# Thesis_HarvestEvaluator.net
KiCad netlist of a schematic drawn in Altium Designer
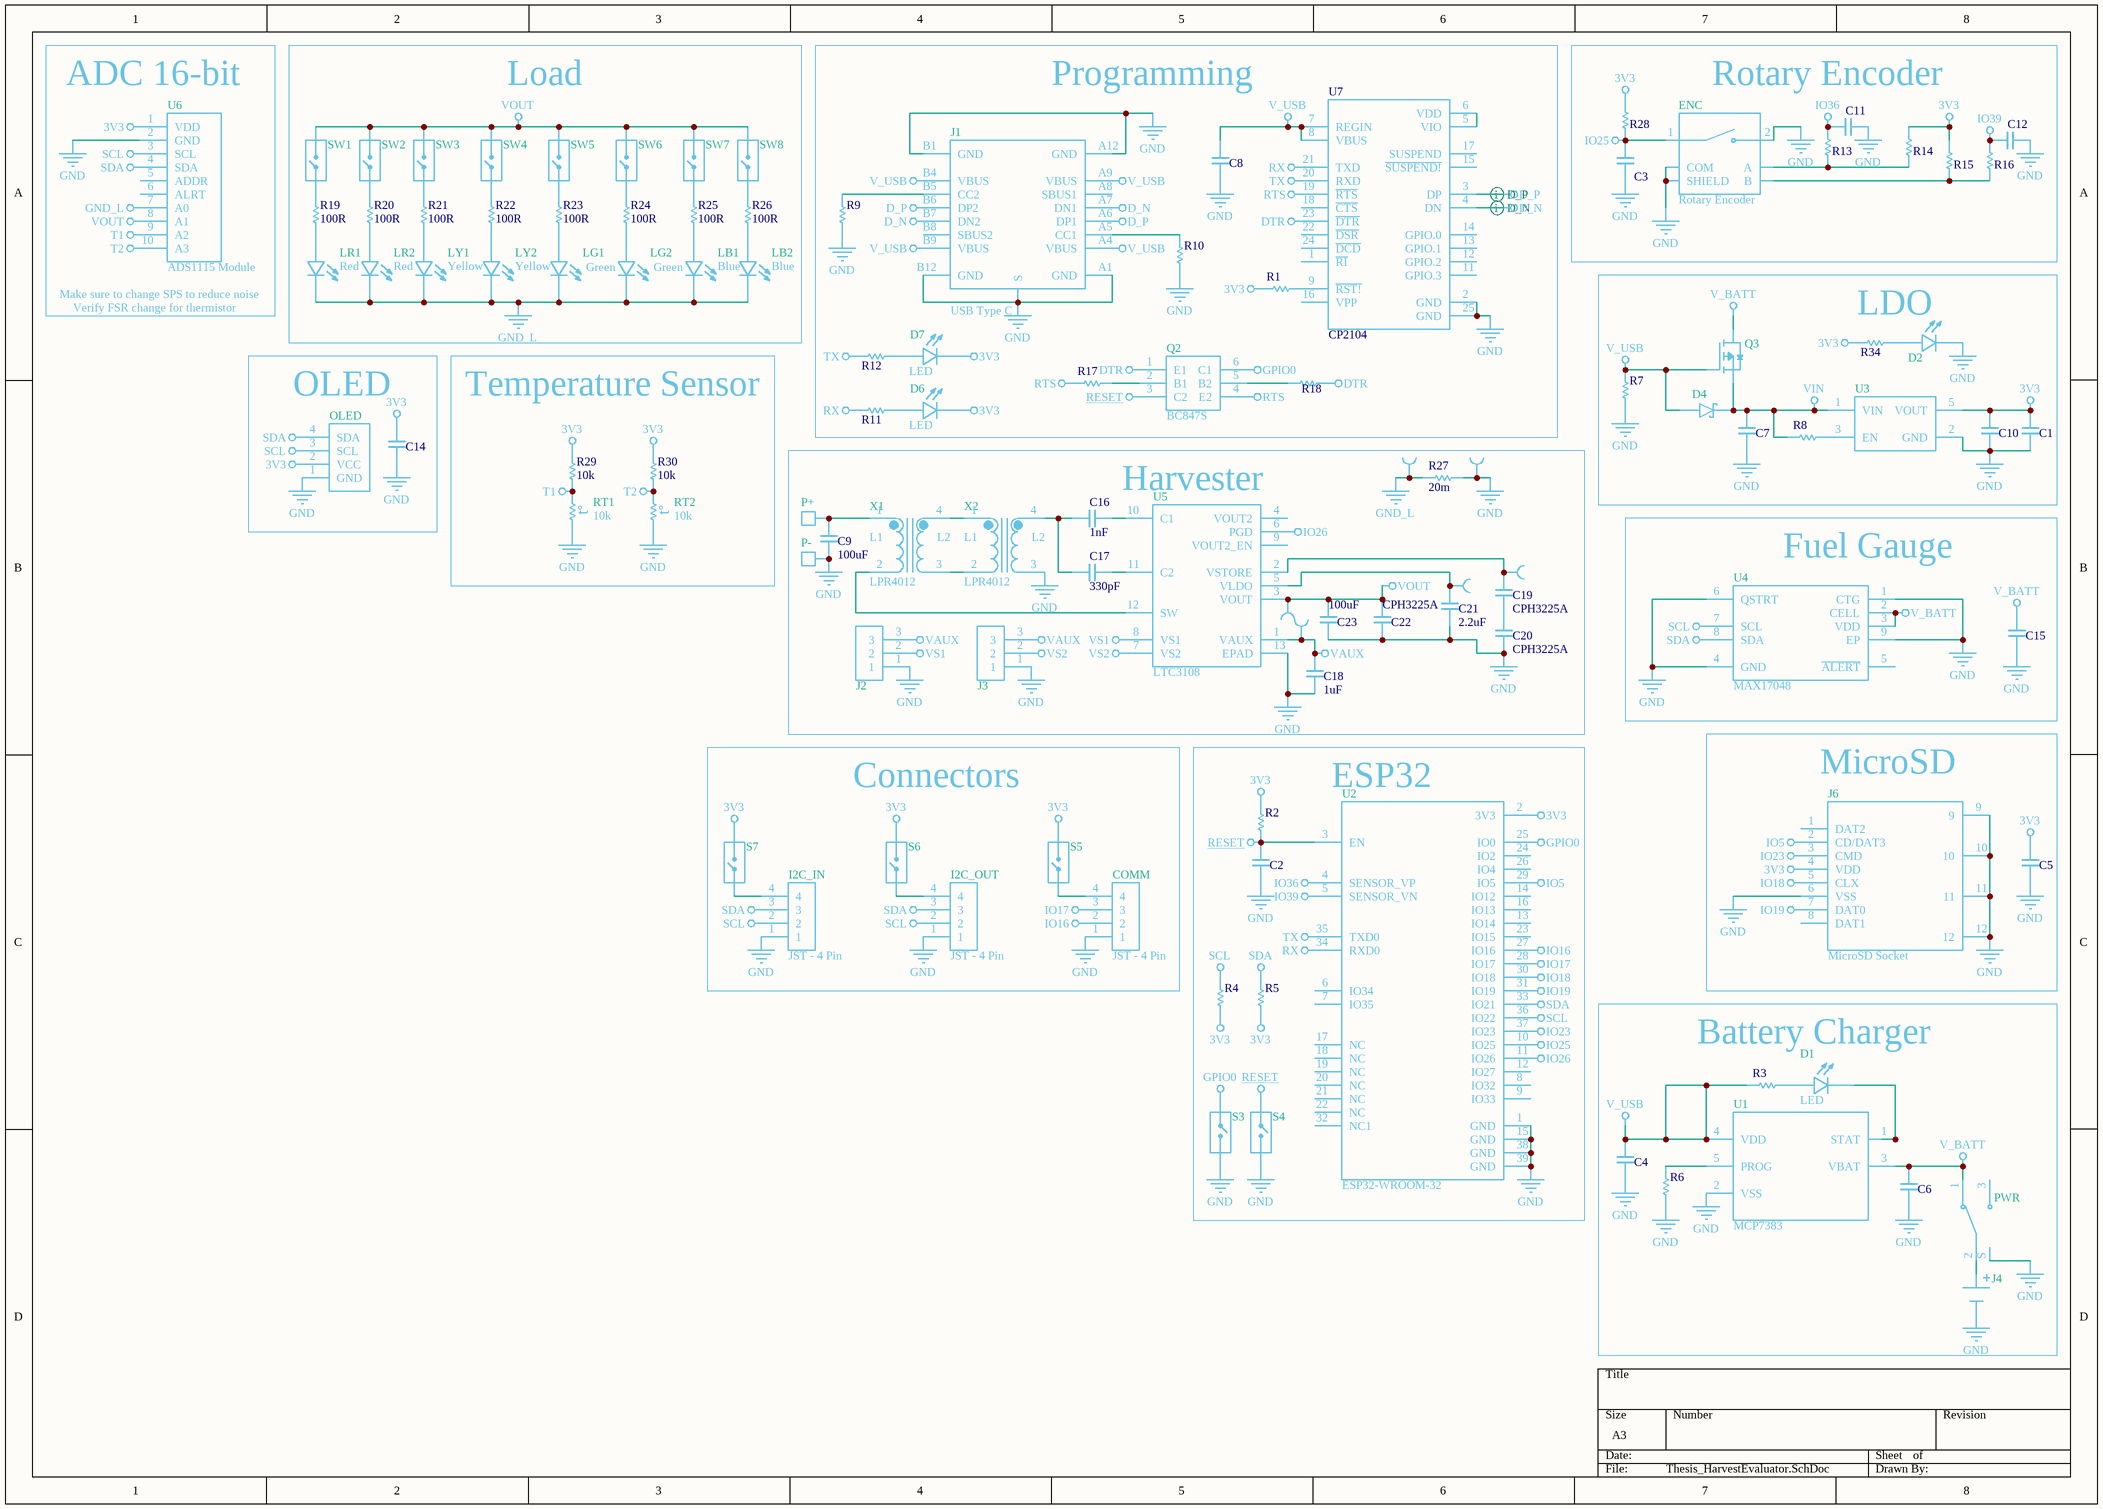
[diagram p0: Thesis_HarvestEvaluator.SchDoc]

(export (version "E")
  (design (tool "Eeschema 10.0.6"))
  (components
    (comp (ref "C1")
      (value "Capacitor")
      (footprint "Capacitor 0402")
      (libsource (lib "LightPack") (part "Capacitor"))
    )
    (comp (ref "C2")
      (value "Capacitor")
      (footprint "Capacitor 0402")
      (libsource (lib "LightPack") (part "Capacitor"))
    )
    (comp (ref "C3")
      (value "Capacitor")
      (footprint "Capacitor 0402")
      (libsource (lib "LightPack") (part "Capacitor"))
    )
    (comp (ref "C4")
      (value "Capacitor")
      (footprint "Capacitor 0603")
      (libsource (lib "LightPack") (part "Capacitor"))
    )
    (comp (ref "C5")
      (value "Capacitor")
      (footprint "Capacitor 0402")
      (libsource (lib "LightPack") (part "Capacitor"))
    )
    (comp (ref "C6")
      (value "Capacitor")
      (footprint "Capacitor 0402")
      (libsource (lib "LightPack") (part "Capacitor"))
    )
    (comp (ref "C7")
      (value "Capacitor")
      (footprint "Capacitor 0402")
      (libsource (lib "LightPack") (part "Capacitor"))
    )
    (comp (ref "C8")
      (value "Capacitor")
      (footprint "Capacitor 0402")
      (libsource (lib "LightPack") (part "Capacitor"))
    )
    (comp (ref "C9")
      (value "100uF")
      (footprint "Capacitor 0805")
      (libsource (lib "Krill") (part "Capacitor"))
    )
    (comp (ref "C10")
      (value "Capacitor")
      (footprint "Capacitor 0402")
      (libsource (lib "LightPack") (part "Capacitor"))
    )
    (comp (ref "C11")
      (value "Capacitor")
      (footprint "Capacitor 0402")
      (libsource (lib "") (part "Capacitor_1"))
    )
    (comp (ref "C12")
      (value "Capacitor")
      (footprint "Capacitor 0402")
      (libsource (lib "") (part "Capacitor_1"))
    )
    (comp (ref "C14")
      (value "Capacitor")
      (footprint "Capacitor 0402")
      (libsource (lib "LightPack") (part "Capacitor"))
    )
    (comp (ref "C15")
      (value "Capacitor")
      (footprint "Capacitor 0402")
      (libsource (lib "LightPack") (part "Capacitor"))
    )
    (comp (ref "C16") (value "1nF") (footprint "Capacitor 0402") (libsource (lib "") (part "Capacitor_1")))
    (comp (ref "C17") (value "330pF") (footprint "Capacitor 0402") (libsource (lib "") (part "Capacitor_1")))
    (comp (ref "C18") (value "1uF") (footprint "Capacitor 0402") (libsource (lib "Krill") (part "Capacitor")))
    (comp (ref "C19") (value "CPH3225A") (footprint "CPH3225A") (libsource (lib "Krill") (part "Capacitor")))
    (comp (ref "C20") (value "CPH3225A") (footprint "CPH3225A") (libsource (lib "Krill") (part "Capacitor")))
    (comp (ref "C21")
      (value "2.2uF")
      (footprint "Capacitor 0402")
      (libsource (lib "Krill") (part "Capacitor"))
    )
    (comp (ref "C22") (value "CPH3225A") (footprint "CPH3225A") (libsource (lib "Krill") (part "Capacitor")))
    (comp (ref "C23")
      (value "100uF")
      (footprint "Capacitor 0805")
      (libsource (lib "Krill") (part "Capacitor"))
    )
    (comp (ref "COMM")
      (value "JST - 4 Pin")
      (footprint "B4B-PH")
      (libsource (lib "LightPack") (part "JST - 4 Pin"))
    )
    (comp (ref "D1") (value "LED") (footprint "LED 0603 - Yellow") (libsource (lib "LightPack") (part "LED")))
    (comp (ref "D2") (value "LED") (footprint "LED 0603 - Red") (libsource (lib "LightPack") (part "LED")))
    (comp (ref "D4")
      (value "Schottky Diode")
      (footprint "BAT60B")
      (libsource (lib "LightPack") (part "Schottky Diode"))
    )
    (comp (ref "D6") (value "LED") (footprint "LED 0603 - Green") (libsource (lib "LightPack") (part "LED")))
    (comp (ref "D7") (value "LED") (footprint "LED 0603 - Green") (libsource (lib "LightPack") (part "LED")))
    (comp (ref "ENC")
      (value "Rotary Encoder")
      (footprint "PEC11R-4215F-S0024")
      (libsource (lib "LightPack") (part "Rotary Encoder"))
    )
    (comp (ref "I2C_IN")
      (value "JST - 4 Pin")
      (footprint "S4B-PH")
      (libsource (lib "LightPack") (part "JST - 4 Pin"))
    )
    (comp (ref "I2C_OUT")
      (value "JST - 4 Pin")
      (footprint "S4B-PH")
      (libsource (lib "LightPack") (part "JST - 4 Pin"))
    )
    (comp (ref "J1")
      (value "USB Type C")
      (footprint "USB Type C")
      (libsource (lib "LightPack") (part "USB Type C"))
    )
    (comp (ref "J2")
      (value "Male Header - 3 Pin")
      (footprint "Male Header - 3 Pin")
      (libsource (lib "Krill") (part "Male Header - 3 Pin"))
    )
    (comp (ref "J3")
      (value "Male Header - 3 Pin")
      (footprint "Male Header - 3 Pin")
      (libsource (lib "Krill") (part "Male Header - 3 Pin"))
    )
    (comp (ref "J4")
      (value "BH-18650")
      (footprint "BH-18650 - No hole")
      (libsource (lib "LightPack") (part "BH-18650"))
    )
    (comp (ref "J6")
      (value "MicroSD Socket")
      (footprint "MicroSD Socket")
      (libsource (lib "LightPack") (part "MicroSD Socket"))
    )
    (comp (ref "LB1") (value "Blue") (footprint "LED 0603 - Blue") (libsource (lib "Krill") (part "LED")))
    (comp (ref "LB2") (value "Blue") (footprint "LED 0603 - Blue") (libsource (lib "Krill") (part "LED")))
    (comp (ref "LG1") (value "Green") (footprint "LED 0603 - Green") (libsource (lib "Krill") (part "LED")))
    (comp (ref "LG2") (value "Green") (footprint "LED 0603 - Green") (libsource (lib "Krill") (part "LED")))
    (comp (ref "LR1") (value "Red") (footprint "LED 0603 - Red") (libsource (lib "Krill") (part "LED")))
    (comp (ref "LR2") (value "Red") (footprint "LED 0603 - Red") (libsource (lib "Krill") (part "LED")))
    (comp (ref "LY1") (value "Yellow") (footprint "LED 0603 - Yellow") (libsource (lib "Krill") (part "LED")))
    (comp (ref "LY2") (value "Yellow") (footprint "LED 0603 - Yellow") (libsource (lib "Krill") (part "LED")))
    (comp (ref "OLED")
      (value "OLED I2C")
      (footprint "OLED 1.3in module")
      (libsource (lib "LightPack") (part "OLED I2C"))
    )
    (comp (ref "P+") (value "Pad") (footprint "Pad") (libsource (lib "Krill") (part "Pad")))
    (comp (ref "P-") (value "Pad") (footprint "Pad") (libsource (lib "Krill") (part "Pad")))
    (comp (ref "PWR")
      (value "Switch - Horizontal")
      (footprint "MK-12C02-G015")
      (libsource (lib "LightPack") (part "Switch - Horizontal"))
    )
    (comp (ref "Q2") (value "BC847S") (footprint "BC847S") (libsource (lib "LightPack") (part "BC847S")))
    (comp (ref "Q3") (value "DMG230") (footprint "DMG230") (libsource (lib "LightPack") (part "DMG230")))
    (comp (ref "R1")
      (value "Resistor")
      (footprint "Resistor 0402")
      (libsource (lib "LightPack") (part "Resistor"))
    )
    (comp (ref "R2")
      (value "Resistor")
      (footprint "Resistor 0402")
      (libsource (lib "LightPack") (part "Resistor"))
    )
    (comp (ref "R3")
      (value "Resistor")
      (footprint "Resistor 0402")
      (libsource (lib "LightPack") (part "Resistor"))
    )
    (comp (ref "R4")
      (value "Resistor")
      (footprint "Resistor 0402")
      (libsource (lib "LightPack") (part "Resistor"))
    )
    (comp (ref "R5")
      (value "Resistor")
      (footprint "Resistor 0402")
      (libsource (lib "LightPack") (part "Resistor"))
    )
    (comp (ref "R6")
      (value "Resistor")
      (footprint "Resistor 0603")
      (libsource (lib "LightPack") (part "Resistor"))
    )
    (comp (ref "R7")
      (value "Resistor")
      (footprint "Resistor 0402")
      (libsource (lib "LightPack") (part "Resistor"))
    )
    (comp (ref "R8")
      (value "Resistor")
      (footprint "Resistor 0402")
      (libsource (lib "LightPack") (part "Resistor"))
    )
    (comp (ref "R9")
      (value "Resistor")
      (footprint "Resistor 0402")
      (libsource (lib "LightPack") (part "Resistor"))
    )
    (comp (ref "R10")
      (value "Resistor")
      (footprint "Resistor 0402")
      (libsource (lib "LightPack") (part "Resistor"))
    )
    (comp (ref "R11")
      (value "Resistor")
      (footprint "Resistor 0402")
      (libsource (lib "LightPack") (part "Resistor"))
    )
    (comp (ref "R12")
      (value "Resistor")
      (footprint "Resistor 0402")
      (libsource (lib "LightPack") (part "Resistor"))
    )
    (comp (ref "R13")
      (value "Resistor")
      (footprint "Resistor 0402")
      (libsource (lib "LightPack") (part "Resistor"))
    )
    (comp (ref "R14")
      (value "Resistor")
      (footprint "Resistor 0402")
      (libsource (lib "LightPack") (part "Resistor"))
    )
    (comp (ref "R15")
      (value "Resistor")
      (footprint "Resistor 0402")
      (libsource (lib "LightPack") (part "Resistor"))
    )
    (comp (ref "R16")
      (value "Resistor")
      (footprint "Resistor 0402")
      (libsource (lib "LightPack") (part "Resistor"))
    )
    (comp (ref "R17")
      (value "Resistor")
      (footprint "Resistor 0402")
      (libsource (lib "LightPack") (part "Resistor"))
    )
    (comp (ref "R18")
      (value "Resistor")
      (footprint "Resistor 0402")
      (libsource (lib "LightPack") (part "Resistor"))
    )
    (comp (ref "R19")
      (value "100R")
      (footprint "Resistor 0402")
      (description "May be 0R or 1k")
      (libsource (lib "Krill") (part "Resistor"))
    )
    (comp (ref "R20")
      (value "100R")
      (footprint "Resistor 0402")
      (description "May be 0R or 1k")
      (libsource (lib "Krill") (part "Resistor"))
    )
    (comp (ref "R21")
      (value "100R")
      (footprint "Resistor 0402")
      (description "May be 0R or 1k")
      (libsource (lib "Krill") (part "Resistor"))
    )
    (comp (ref "R22")
      (value "100R")
      (footprint "Resistor 0402")
      (description "May be 0R or 1k")
      (libsource (lib "Krill") (part "Resistor"))
    )
    (comp (ref "R23")
      (value "100R")
      (footprint "Resistor 0402")
      (description "May be 0R or 1k")
      (libsource (lib "Krill") (part "Resistor"))
    )
    (comp (ref "R24")
      (value "100R")
      (footprint "Resistor 0402")
      (description "May be 0R or 1k")
      (libsource (lib "Krill") (part "Resistor"))
    )
    (comp (ref "R25")
      (value "100R")
      (footprint "Resistor 0402")
      (description "May be 0R or 1k")
      (libsource (lib "Krill") (part "Resistor"))
    )
    (comp (ref "R26")
      (value "100R")
      (footprint "Resistor 0402")
      (description "May be 0R or 1k")
      (libsource (lib "Krill") (part "Resistor"))
    )
    (comp (ref "R27")
      (value "20m")
      (footprint "Resistor 0402")
      (description "Consider different shunt ranges")
      (libsource (lib "Krill") (part "Resistor"))
    )
    (comp (ref "R28")
      (value "Resistor")
      (footprint "Resistor 0402")
      (libsource (lib "LightPack") (part "Resistor"))
    )
    (comp (ref "R29")
      (value "10k")
      (footprint "Resistor 0402")
      (description "May be 0R or 1k")
      (libsource (lib "Krill") (part "Resistor"))
    )
    (comp (ref "R30")
      (value "10k")
      (footprint "Resistor 0402")
      (description "May be 0R or 1k")
      (libsource (lib "Krill") (part "Resistor"))
    )
    (comp (ref "R34")
      (value "Resistor")
      (footprint "Resistor 0402")
      (libsource (lib "LightPack") (part "Resistor"))
    )
    (comp (ref "RT1") (value "10k") (footprint "S2B-PH") (libsource (lib "Krill") (part "Thermistor")))
    (comp (ref "RT2") (value "10k") (footprint "S2B-PH") (libsource (lib "Krill") (part "Thermistor")))
    (comp (ref "S3")
      (value "Switch - 2 pin")
      (footprint "Push Button 3.5x6")
      (libsource (lib "LightPack") (part "Switch - 2 pin"))
    )
    (comp (ref "S4")
      (value "Switch - 2 pin")
      (footprint "Push Button 3.5x6")
      (libsource (lib "LightPack") (part "Switch - 2 pin"))
    )
    (comp (ref "S5")
      (value "Switch - 2 pin")
      (footprint "Male Header - 2 Pin")
      (libsource (lib "LightPack") (part "Switch - 2 pin"))
    )
    (comp (ref "S6")
      (value "Switch - 2 pin")
      (footprint "Male Header - 2 Pin")
      (libsource (lib "LightPack") (part "Switch - 2 pin"))
    )
    (comp (ref "S7")
      (value "Switch - 2 pin")
      (footprint "Male Header - 2 Pin")
      (libsource (lib "LightPack") (part "Switch - 2 pin"))
    )
    (comp (ref "SW1")
      (value "Switch - 2 pin")
      (footprint "Male Header - 2 Pin")
      (libsource (lib "Krill") (part "Switch - 2 pin"))
    )
    (comp (ref "SW2")
      (value "Switch - 2 pin")
      (footprint "Male Header - 2 Pin")
      (libsource (lib "Krill") (part "Switch - 2 pin"))
    )
    (comp (ref "SW3")
      (value "Switch - 2 pin")
      (footprint "Male Header - 2 Pin")
      (libsource (lib "Krill") (part "Switch - 2 pin"))
    )
    (comp (ref "SW4")
      (value "Switch - 2 pin")
      (footprint "Male Header - 2 Pin")
      (libsource (lib "Krill") (part "Switch - 2 pin"))
    )
    (comp (ref "SW5")
      (value "Switch - 2 pin")
      (footprint "Male Header - 2 Pin")
      (libsource (lib "Krill") (part "Switch - 2 pin"))
    )
    (comp (ref "SW6")
      (value "Switch - 2 pin")
      (footprint "Male Header - 2 Pin")
      (libsource (lib "Krill") (part "Switch - 2 pin"))
    )
    (comp (ref "SW7")
      (value "Switch - 2 pin")
      (footprint "Male Header - 2 Pin")
      (libsource (lib "Krill") (part "Switch - 2 pin"))
    )
    (comp (ref "SW8")
      (value "Switch - 2 pin")
      (footprint "Male Header - 2 Pin")
      (libsource (lib "Krill") (part "Switch - 2 pin"))
    )
    (comp (ref "TP1")
      (value "Keystone 5001")
      (footprint "Keystone 5001")
      (libsource (lib "Krill") (part "Keystone 5001"))
    )
    (comp (ref "TP2")
      (value "Keystone 5001")
      (footprint "Keystone 5001")
      (libsource (lib "Krill") (part "Keystone 5001"))
    )
    (comp (ref "TP3")
      (value "Keystone 5001")
      (footprint "Keystone 5001")
      (libsource (lib "Krill") (part "Keystone 5001"))
    )
    (comp (ref "TP4")
      (value "Keystone 5001")
      (footprint "Keystone 5001")
      (libsource (lib "Krill") (part "Keystone 5001"))
    )
    (comp (ref "TP5")
      (value "Keystone 5001")
      (footprint "Keystone 5001")
      (libsource (lib "Krill") (part "Keystone 5001"))
    )
    (comp (ref "TP6")
      (value "Keystone 5001")
      (footprint "Keystone 5001")
      (libsource (lib "Krill") (part "Keystone 5001"))
    )
    (comp (ref "U1") (value "MCP7383") (footprint "MCP7383") (libsource (lib "LightPack") (part "MCP7383")))
    (comp (ref "U2")
      (value "ESP32-WROOM-32")
      (footprint "ESP32-WROOM-32D")
      (libsource (lib "LightPack") (part "ESP32-WROOM-32"))
    )
    (comp (ref "U3") (value "XC6220") (footprint "XC6220") (libsource (lib "LightPack") (part "XC6220")))
    (comp (ref "U4")
      (value "MAX17048")
      (footprint "MAX17048")
      (libsource (lib "LightPack") (part "MAX17048"))
    )
    (comp (ref "U5") (value "LTC3108") (footprint "LTC3108") (libsource (lib "Krill") (part "LTC3108")))
    (comp (ref "U6")
      (value "ADS1115 Module")
      (footprint "ADS1115 Module - No Hole")
      (libsource (lib "Krill") (part "ADS1115 Module"))
    )
    (comp (ref "U7") (value "CP2104") (footprint "CP2104") (libsource (lib "LightPack") (part "CP2104")))
    (comp (ref "X1") (value "LPR4012") (footprint "LPR4012") (libsource (lib "Krill") (part "LPR4012")))
    (comp (ref "X2") (value "LPR4012") (footprint "LPR4012") (libsource (lib "Krill") (part "LPR4012")))
  )
  (nets
    (net (code "1") (name "3V3") (class "Default")
      (node (ref "C1") (pin "1") (pinfunction "1_1") (pintype "passive"))
      (node (ref "C10") (pin "1") (pinfunction "1_1") (pintype "passive"))
      (node (ref "C14") (pin "1") (pinfunction "1_1") (pintype "passive"))
      (node (ref "C5") (pin "1") (pinfunction "1_1") (pintype "passive"))
      (node (ref "D6") (pin "C") (pinfunction "C_C") (pintype "passive"))
      (node (ref "D7") (pin "C") (pinfunction "C_C") (pintype "passive"))
      (node (ref "J6") (pin "4") (pinfunction "VDD_4") (pintype "passive"))
      (node (ref "OLED") (pin "2") (pinfunction "VCC_2") (pintype "passive"))
      (node (ref "R1") (pin "1") (pinfunction "1_1") (pintype "passive"))
      (node (ref "R14") (pin "2") (pinfunction "2_2") (pintype "passive"))
      (node (ref "R15") (pin "2") (pinfunction "2_2") (pintype "passive"))
      (node (ref "R2") (pin "2") (pinfunction "2_2") (pintype "passive"))
      (node (ref "R28") (pin "2") (pinfunction "2_2") (pintype "passive"))
      (node (ref "R29") (pin "2") (pinfunction "2_2") (pintype "passive"))
      (node (ref "R30") (pin "2") (pinfunction "2_2") (pintype "passive"))
      (node (ref "R34") (pin "2") (pinfunction "2_2") (pintype "passive"))
      (node (ref "R4") (pin "1") (pinfunction "1_1") (pintype "passive"))
      (node (ref "R5") (pin "1") (pinfunction "1_1") (pintype "passive"))
      (node (ref "S5") (pin "2") (pinfunction "2_2") (pintype "passive"))
      (node (ref "S6") (pin "2") (pinfunction "2_2") (pintype "passive"))
      (node (ref "S7") (pin "2") (pinfunction "2_2") (pintype "passive"))
      (node (ref "U2") (pin "2") (pinfunction "3V3_2") (pintype "passive"))
      (node (ref "U3") (pin "5") (pinfunction "VOUT_5") (pintype "passive"))
      (node (ref "U6") (pin "1") (pinfunction "VDD_1") (pintype "passive"))
    )
    (net (code "2") (name "DTR") (class "Default")
      (node (ref "Q2") (pin "1") (pinfunction "E1_1") (pintype "passive"))
      (node (ref "R18") (pin "2") (pinfunction "2_2") (pintype "passive"))
      (node (ref "U7") (pin "23") (pinfunction "~{DTR}_23") (pintype "passive"))
    )
    (net (code "3") (name "D_N") (class "Default")
      (node (ref "J1") (pin "A7") (pinfunction "DN1_A7") (pintype "passive"))
      (node (ref "J1") (pin "B7") (pinfunction "DN2_B7") (pintype "passive"))
      (node (ref "U7") (pin "4") (pinfunction "DN_4") (pintype "passive"))
    )
    (net (code "4") (name "D_P") (class "Default")
      (node (ref "J1") (pin "A6") (pinfunction "DP1_A6") (pintype "passive"))
      (node (ref "J1") (pin "B6") (pinfunction "DP2_B6") (pintype "passive"))
      (node (ref "U7") (pin "3") (pinfunction "DP_3") (pintype "passive"))
    )
    (net (code "5") (name "GND") (class "Default")
      (node (ref "C1") (pin "2") (pinfunction "2_2") (pintype "passive"))
      (node (ref "C10") (pin "2") (pinfunction "2_2") (pintype "passive"))
      (node (ref "C11") (pin "1") (pinfunction "1_1") (pintype "passive"))
      (node (ref "C12") (pin "1") (pinfunction "1_1") (pintype "passive"))
      (node (ref "C14") (pin "2") (pinfunction "2_2") (pintype "passive"))
      (node (ref "C15") (pin "2") (pinfunction "2_2") (pintype "passive"))
      (node (ref "C18") (pin "2") (pinfunction "2_2") (pintype "passive"))
      (node (ref "C2") (pin "2") (pinfunction "2_2") (pintype "passive"))
      (node (ref "C20") (pin "2") (pinfunction "2_2") (pintype "passive"))
      (node (ref "C21") (pin "2") (pinfunction "2_2") (pintype "passive"))
      (node (ref "C22") (pin "2") (pinfunction "2_2") (pintype "passive"))
      (node (ref "C23") (pin "2") (pinfunction "2_2") (pintype "passive"))
      (node (ref "C3") (pin "2") (pinfunction "2_2") (pintype "passive"))
      (node (ref "C4") (pin "2") (pinfunction "2_2") (pintype "passive"))
      (node (ref "C5") (pin "2") (pinfunction "2_2") (pintype "passive"))
      (node (ref "C6") (pin "2") (pinfunction "2_2") (pintype "passive"))
      (node (ref "C7") (pin "2") (pinfunction "2_2") (pintype "passive"))
      (node (ref "C8") (pin "2") (pinfunction "2_2") (pintype "passive"))
      (node (ref "C9") (pin "2") (pinfunction "2_2") (pintype "passive"))
      (node (ref "COMM") (pin "1") (pinfunction "1_1") (pintype "passive"))
      (node (ref "D2") (pin "C") (pinfunction "C_C") (pintype "passive"))
      (node (ref "ENC") (pin "2") (pinfunction "2_2") (pintype "passive"))
      (node (ref "ENC") (pin "COM") (pinfunction "COM_COM") (pintype "passive"))
      (node (ref "ENC") (pin "S") (pinfunction "SHIELD_S") (pintype "passive"))
      (node (ref "I2C_IN") (pin "1") (pinfunction "1_1") (pintype "passive"))
      (node (ref "I2C_OUT") (pin "1") (pinfunction "1_1") (pintype "passive"))
      (node (ref "J1") (pin "A1") (pinfunction "GND_A1") (pintype "passive"))
      (node (ref "J1") (pin "A12") (pinfunction "GND_A12") (pintype "passive"))
      (node (ref "J1") (pin "B1") (pinfunction "GND_B1") (pintype "passive"))
      (node (ref "J1") (pin "B12") (pinfunction "GND_B12") (pintype "passive"))
      (node (ref "J1") (pin "S") (pinfunction "S_S") (pintype "passive"))
      (node (ref "J2") (pin "1") (pinfunction "1_1") (pintype "passive"))
      (node (ref "J3") (pin "1") (pinfunction "1_1") (pintype "passive"))
      (node (ref "J4") (pin "N") (pinfunction "NEG_N") (pintype "passive"))
      (node (ref "J6") (pin "10") (pinfunction "10_10") (pintype "passive"))
      (node (ref "J6") (pin "11") (pinfunction "11_11") (pintype "passive"))
      (node (ref "J6") (pin "12") (pinfunction "12_12") (pintype "passive"))
      (node (ref "J6") (pin "6") (pinfunction "VSS_6") (pintype "passive"))
      (node (ref "J6") (pin "9") (pinfunction "9_9") (pintype "passive"))
      (node (ref "OLED") (pin "1") (pinfunction "GND_1") (pintype "passive"))
      (node (ref "P-") (pin "1") (pintype "passive"))
      (node (ref "PWR") (pin "S") (pinfunction "S_S") (pintype "passive"))
      (node (ref "R10") (pin "1") (pinfunction "1_1") (pintype "passive"))
      (node (ref "R27") (pin "1") (pinfunction "1_1") (pintype "passive"))
      (node (ref "R6") (pin "1") (pinfunction "1_1") (pintype "passive"))
      (node (ref "R7") (pin "1") (pinfunction "1_1") (pintype "passive"))
      (node (ref "R9") (pin "1") (pinfunction "1_1") (pintype "passive"))
      (node (ref "RT1") (pin "1") (pinfunction "1_1") (pintype "passive"))
      (node (ref "RT2") (pin "1") (pinfunction "1_1") (pintype "passive"))
      (node (ref "S3") (pin "2") (pinfunction "2_2") (pintype "passive"))
      (node (ref "S4") (pin "2") (pinfunction "2_2") (pintype "passive"))
      (node (ref "TP6") (pin "1") (pinfunction "1_1") (pintype "passive"))
      (node (ref "U1") (pin "2") (pinfunction "VSS_2") (pintype "passive"))
      (node (ref "U2") (pin "1") (pinfunction "GND_1") (pintype "passive"))
      (node (ref "U2") (pin "15") (pinfunction "GND_15") (pintype "passive"))
      (node (ref "U2") (pin "38") (pinfunction "GND_38") (pintype "passive"))
      (node (ref "U2") (pin "39") (pinfunction "GND_39") (pintype "passive"))
      (node (ref "U3") (pin "2") (pinfunction "GND_2") (pintype "passive"))
      (node (ref "U4") (pin "1") (pinfunction "CTG_1") (pintype "passive"))
      (node (ref "U4") (pin "4") (pinfunction "GND_4") (pintype "passive"))
      (node (ref "U4") (pin "6") (pinfunction "QSTRT_6") (pintype "passive"))
      (node (ref "U4") (pin "9") (pinfunction "EP_9") (pintype "passive"))
      (node (ref "U5") (pin "13") (pinfunction "EPAD_13") (pintype "passive"))
      (node (ref "U6") (pin "2") (pinfunction "GND_2") (pintype "passive"))
      (node (ref "U7") (pin "2") (pinfunction "GND_2") (pintype "passive"))
      (node (ref "U7") (pin "25") (pinfunction "GND_25") (pintype "passive"))
      (node (ref "X2") (pin "3") (pinfunction "3_3") (pintype "passive"))
    )
    (net (code "6") (name "GND_L") (class "Default")
      (node (ref "LB1") (pin "C") (pinfunction "C_C") (pintype "passive"))
      (node (ref "LB2") (pin "C") (pinfunction "C_C") (pintype "passive"))
      (node (ref "LG1") (pin "C") (pinfunction "C_C") (pintype "passive"))
      (node (ref "LG2") (pin "C") (pinfunction "C_C") (pintype "passive"))
      (node (ref "LR1") (pin "C") (pinfunction "C_C") (pintype "passive"))
      (node (ref "LR2") (pin "C") (pinfunction "C_C") (pintype "passive"))
      (node (ref "LY1") (pin "C") (pinfunction "C_C") (pintype "passive"))
      (node (ref "LY2") (pin "C") (pinfunction "C_C") (pintype "passive"))
      (node (ref "R27") (pin "2") (pinfunction "2_2") (pintype "passive"))
      (node (ref "TP5") (pin "1") (pinfunction "1_1") (pintype "passive"))
      (node (ref "U6") (pin "7") (pinfunction "A0_7") (pintype "passive"))
    )
    (net (code "7") (name "GPIO0") (class "Default")
      (node (ref "Q2") (pin "6") (pinfunction "C1_6") (pintype "passive"))
      (node (ref "S3") (pin "1") (pinfunction "1_1") (pintype "passive"))
      (node (ref "U2") (pin "25") (pinfunction "IO0_25") (pintype "passive"))
    )
    (net (code "8") (name "IO5") (class "Default")
      (node (ref "J6") (pin "2") (pinfunction "CD/DAT3_2") (pintype "passive"))
      (node (ref "U2") (pin "29") (pinfunction "IO5_29") (pintype "passive"))
    )
    (net (code "9") (name "IO16") (class "Default")
      (node (ref "COMM") (pin "2") (pinfunction "2_2") (pintype "passive"))
      (node (ref "U2") (pin "27") (pinfunction "IO16_27") (pintype "passive"))
    )
    (net (code "10") (name "IO17") (class "Default")
      (node (ref "COMM") (pin "3") (pinfunction "3_3") (pintype "passive"))
      (node (ref "U2") (pin "28") (pinfunction "IO17_28") (pintype "passive"))
    )
    (net (code "11") (name "IO18") (class "Default")
      (node (ref "J6") (pin "5") (pinfunction "CLX_5") (pintype "passive"))
      (node (ref "U2") (pin "30") (pinfunction "IO18_30") (pintype "passive"))
    )
    (net (code "12") (name "IO19") (class "Default")
      (node (ref "J6") (pin "7") (pinfunction "DAT0_7") (pintype "passive"))
      (node (ref "U2") (pin "31") (pinfunction "IO19_31") (pintype "passive"))
    )
    (net (code "13") (name "IO23") (class "Default")
      (node (ref "J6") (pin "3") (pinfunction "CMD_3") (pintype "passive"))
      (node (ref "U2") (pin "37") (pinfunction "IO23_37") (pintype "passive"))
    )
    (net (code "14") (name "IO25") (class "Default")
      (node (ref "C3") (pin "1") (pinfunction "1_1") (pintype "passive"))
      (node (ref "ENC") (pin "1") (pinfunction "1_1") (pintype "passive"))
      (node (ref "R28") (pin "1") (pinfunction "1_1") (pintype "passive"))
      (node (ref "U2") (pin "10") (pinfunction "IO25_10") (pintype "passive"))
    )
    (net (code "15") (name "IO26") (class "Default")
      (node (ref "U2") (pin "11") (pinfunction "IO26_11") (pintype "passive"))
      (node (ref "U5") (pin "6") (pinfunction "PGD_6") (pintype "passive"))
    )
    (net (code "16") (name "IO36") (class "Default")
      (node (ref "C11") (pin "2") (pinfunction "2_2") (pintype "passive"))
      (node (ref "R13") (pin "2") (pinfunction "2_2") (pintype "passive"))
      (node (ref "U2") (pin "4") (pinfunction "SENSOR_VP_4") (pintype "passive"))
    )
    (net (code "17") (name "IO39") (class "Default")
      (node (ref "C12") (pin "2") (pinfunction "2_2") (pintype "passive"))
      (node (ref "R16") (pin "1") (pinfunction "1_1") (pintype "passive"))
      (node (ref "U2") (pin "5") (pinfunction "SENSOR_VN_5") (pintype "passive"))
    )
    (net (code "18") (name "Net-(C9-Pad1)") (class "Default")
      (node (ref "C9") (pin "1") (pinfunction "1_1") (pintype "passive"))
      (node (ref "P+") (pin "1") (pintype "passive"))
      (node (ref "X1") (pin "1") (pinfunction "1_1") (pintype "passive"))
    )
    (net (code "19") (name "Net-(C16-Pad2)") (class "Default")
      (node (ref "C16") (pin "2") (pinfunction "2_2") (pintype "passive"))
      (node (ref "C17") (pin "2") (pinfunction "2_2") (pintype "passive"))
      (node (ref "X2") (pin "4") (pinfunction "4_4") (pintype "passive"))
    )
    (net (code "20") (name "Net-(C19-Pad2)") (class "Default")
      (node (ref "C19") (pin "2") (pinfunction "2_2") (pintype "passive"))
      (node (ref "C20") (pin "1") (pinfunction "1_1") (pintype "passive"))
    )
    (net (code "21") (name "Net-(COMM-Pad4)") (class "Default")
      (node (ref "COMM") (pin "4") (pinfunction "4_4") (pintype "passive"))
      (node (ref "S5") (pin "1") (pinfunction "1_1") (pintype "passive"))
    )
    (net (code "22") (name "Net-(D1-PadA)") (class "Default")
      (node (ref "D1") (pin "A") (pinfunction "A_A") (pintype "passive"))
      (node (ref "R3") (pin "2") (pinfunction "2_2") (pintype "passive"))
    )
    (net (code "23") (name "Net-(D2-PadA)") (class "Default")
      (node (ref "D2") (pin "A") (pinfunction "A_A") (pintype "passive"))
      (node (ref "R34") (pin "1") (pinfunction "1_1") (pintype "passive"))
    )
    (net (code "24") (name "Net-(D6-PadA)") (class "Default")
      (node (ref "D6") (pin "A") (pinfunction "A_A") (pintype "passive"))
      (node (ref "R11") (pin "1") (pinfunction "1_1") (pintype "passive"))
    )
    (net (code "25") (name "Net-(D7-PadA)") (class "Default")
      (node (ref "D7") (pin "A") (pinfunction "A_A") (pintype "passive"))
      (node (ref "R12") (pin "1") (pinfunction "1_1") (pintype "passive"))
    )
    (net (code "26") (name "Net-(ENC-PadA)") (class "Default")
      (node (ref "ENC") (pin "A") (pinfunction "A_A") (pintype "passive"))
      (node (ref "R13") (pin "1") (pinfunction "1_1") (pintype "passive"))
      (node (ref "R14") (pin "1") (pinfunction "1_1") (pintype "passive"))
    )
    (net (code "27") (name "Net-(ENC-PadB)") (class "Default")
      (node (ref "ENC") (pin "B") (pinfunction "B_B") (pintype "passive"))
      (node (ref "R15") (pin "1") (pinfunction "1_1") (pintype "passive"))
      (node (ref "R16") (pin "2") (pinfunction "2_2") (pintype "passive"))
    )
    (net (code "28") (name "Net-(I2C_IN-Pad4)") (class "Default")
      (node (ref "I2C_IN") (pin "4") (pinfunction "4_4") (pintype "passive"))
      (node (ref "S7") (pin "1") (pinfunction "1_1") (pintype "passive"))
    )
    (net (code "29") (name "Net-(I2C_OUT-Pad4)") (class "Default")
      (node (ref "I2C_OUT") (pin "4") (pinfunction "4_4") (pintype "passive"))
      (node (ref "S6") (pin "1") (pinfunction "1_1") (pintype "passive"))
    )
    (net (code "30") (name "Net-(J1-CC1)") (class "Default")
      (node (ref "J1") (pin "A5") (pinfunction "CC1_A5") (pintype "passive"))
      (node (ref "R10") (pin "2") (pinfunction "2_2") (pintype "passive"))
    )
    (net (code "31") (name "Net-(J1-CC2)") (class "Default")
      (node (ref "J1") (pin "B5") (pinfunction "CC2_B5") (pintype "passive"))
      (node (ref "R9") (pin "2") (pinfunction "2_2") (pintype "passive"))
    )
    (net (code "32") (name "Net-(J4-POS)") (class "Default")
      (node (ref "J4") (pin "P") (pinfunction "POS_P") (pintype "passive"))
      (node (ref "PWR") (pin "2") (pinfunction "2_2") (pintype "passive"))
    )
    (net (code "33") (name "Net-(LB1-PadA)") (class "Default")
      (node (ref "LB1") (pin "A") (pinfunction "A_A") (pintype "passive"))
      (node (ref "R25") (pin "1") (pinfunction "1_1") (pintype "passive"))
    )
    (net (code "34") (name "Net-(LB2-PadA)") (class "Default")
      (node (ref "LB2") (pin "A") (pinfunction "A_A") (pintype "passive"))
      (node (ref "R26") (pin "1") (pinfunction "1_1") (pintype "passive"))
    )
    (net (code "35") (name "Net-(LG1-PadA)") (class "Default")
      (node (ref "LG1") (pin "A") (pinfunction "A_A") (pintype "passive"))
      (node (ref "R23") (pin "1") (pinfunction "1_1") (pintype "passive"))
    )
    (net (code "36") (name "Net-(LG2-PadA)") (class "Default")
      (node (ref "LG2") (pin "A") (pinfunction "A_A") (pintype "passive"))
      (node (ref "R24") (pin "1") (pinfunction "1_1") (pintype "passive"))
    )
    (net (code "37") (name "Net-(LR1-PadA)") (class "Default")
      (node (ref "LR1") (pin "A") (pinfunction "A_A") (pintype "passive"))
      (node (ref "R19") (pin "1") (pinfunction "1_1") (pintype "passive"))
    )
    (net (code "38") (name "Net-(LR2-PadA)") (class "Default")
      (node (ref "LR2") (pin "A") (pinfunction "A_A") (pintype "passive"))
      (node (ref "R20") (pin "1") (pinfunction "1_1") (pintype "passive"))
    )
    (net (code "39") (name "Net-(LY1-PadA)") (class "Default")
      (node (ref "LY1") (pin "A") (pinfunction "A_A") (pintype "passive"))
      (node (ref "R21") (pin "1") (pinfunction "1_1") (pintype "passive"))
    )
    (net (code "40") (name "Net-(LY2-PadA)") (class "Default")
      (node (ref "LY2") (pin "A") (pinfunction "A_A") (pintype "passive"))
      (node (ref "R22") (pin "1") (pinfunction "1_1") (pintype "passive"))
    )
    (net (code "41") (name "Net-(Q2-B1)") (class "Default")
      (node (ref "Q2") (pin "2") (pinfunction "B1_2") (pintype "passive"))
      (node (ref "R17") (pin "2") (pinfunction "2_2") (pintype "passive"))
    )
    (net (code "42") (name "Net-(Q2-B2)") (class "Default")
      (node (ref "Q2") (pin "5") (pinfunction "B2_5") (pintype "passive"))
      (node (ref "R18") (pin "1") (pinfunction "1_1") (pintype "passive"))
    )
    (net (code "43") (name "Net-(R19-Pad2)") (class "Default")
      (node (ref "R19") (pin "2") (pinfunction "2_2") (pintype "passive"))
      (node (ref "SW1") (pin "1") (pinfunction "1_1") (pintype "passive"))
    )
    (net (code "44") (name "Net-(R20-Pad2)") (class "Default")
      (node (ref "R20") (pin "2") (pinfunction "2_2") (pintype "passive"))
      (node (ref "SW2") (pin "1") (pinfunction "1_1") (pintype "passive"))
    )
    (net (code "45") (name "Net-(R21-Pad2)") (class "Default")
      (node (ref "R21") (pin "2") (pinfunction "2_2") (pintype "passive"))
      (node (ref "SW3") (pin "1") (pinfunction "1_1") (pintype "passive"))
    )
    (net (code "46") (name "Net-(R22-Pad2)") (class "Default")
      (node (ref "R22") (pin "2") (pinfunction "2_2") (pintype "passive"))
      (node (ref "SW4") (pin "1") (pinfunction "1_1") (pintype "passive"))
    )
    (net (code "47") (name "Net-(R23-Pad2)") (class "Default")
      (node (ref "R23") (pin "2") (pinfunction "2_2") (pintype "passive"))
      (node (ref "SW5") (pin "1") (pinfunction "1_1") (pintype "passive"))
    )
    (net (code "48") (name "Net-(R24-Pad2)") (class "Default")
      (node (ref "R24") (pin "2") (pinfunction "2_2") (pintype "passive"))
      (node (ref "SW6") (pin "1") (pinfunction "1_1") (pintype "passive"))
    )
    (net (code "49") (name "Net-(R25-Pad2)") (class "Default")
      (node (ref "R25") (pin "2") (pinfunction "2_2") (pintype "passive"))
      (node (ref "SW7") (pin "1") (pinfunction "1_1") (pintype "passive"))
    )
    (net (code "50") (name "Net-(R26-Pad2)") (class "Default")
      (node (ref "R26") (pin "2") (pinfunction "2_2") (pintype "passive"))
      (node (ref "SW8") (pin "1") (pinfunction "1_1") (pintype "passive"))
    )
    (net (code "51") (name "Net-(U1-PROG)") (class "Default")
      (node (ref "R6") (pin "2") (pinfunction "2_2") (pintype "passive"))
      (node (ref "U1") (pin "5") (pinfunction "PROG_5") (pintype "passive"))
    )
    (net (code "52") (name "Net-(U1-STAT)") (class "Default")
      (node (ref "D1") (pin "C") (pinfunction "C_C") (pintype "passive"))
      (node (ref "U1") (pin "1") (pinfunction "STAT_1") (pintype "passive"))
    )
    (net (code "53") (name "Net-(U3-EN)") (class "Default")
      (node (ref "R8") (pin "2") (pinfunction "2_2") (pintype "passive"))
      (node (ref "U3") (pin "3") (pinfunction "EN_3") (pintype "passive"))
    )
    (net (code "54") (name "Net-(U5-C1)") (class "Default")
      (node (ref "C16") (pin "1") (pinfunction "1_1") (pintype "passive"))
      (node (ref "U5") (pin "10") (pinfunction "C1_10") (pintype "passive"))
    )
    (net (code "55") (name "Net-(U5-C2)") (class "Default")
      (node (ref "C17") (pin "1") (pinfunction "1_1") (pintype "passive"))
      (node (ref "U5") (pin "11") (pinfunction "C2_11") (pintype "passive"))
    )
    (net (code "56") (name "Net-(U5-SW)") (class "Default")
      (node (ref "U5") (pin "12") (pinfunction "SW_12") (pintype "passive"))
      (node (ref "X1") (pin "2") (pinfunction "2_2") (pintype "passive"))
    )
    (net (code "57") (name "Net-(U5-VLDO)") (class "Default")
      (node (ref "C21") (pin "1") (pinfunction "1_1") (pintype "passive"))
      (node (ref "TP4") (pin "1") (pinfunction "1_1") (pintype "passive"))
      (node (ref "U5") (pin "5") (pinfunction "VLDO_5") (pintype "passive"))
    )
    (net (code "58") (name "Net-(U5-VSTORE)") (class "Default")
      (node (ref "C19") (pin "1") (pinfunction "1_1") (pintype "passive"))
      (node (ref "TP2") (pin "1") (pinfunction "1_1") (pintype "passive"))
      (node (ref "U5") (pin "2") (pinfunction "VSTORE_2") (pintype "passive"))
    )
    (net (code "59") (name "Net-(U7-VDD)") (class "Default")
      (node (ref "U7") (pin "5") (pinfunction "VIO_5") (pintype "passive"))
      (node (ref "U7") (pin "6") (pinfunction "VDD_6") (pintype "passive"))
    )
    (net (code "60") (name "Net-(U7-~{RST!})") (class "Default")
      (node (ref "R1") (pin "2") (pinfunction "2_2") (pintype "passive"))
      (node (ref "U7") (pin "9") (pinfunction "~{RST!}_9") (pintype "passive"))
    )
    (net (code "61") (name "Net-(X1-Pad3)") (class "Default")
      (node (ref "X1") (pin "3") (pinfunction "3_3") (pintype "passive"))
      (node (ref "X2") (pin "2") (pinfunction "2_2") (pintype "passive"))
    )
    (net (code "62") (name "Net-(X1-Pad4)") (class "Default")
      (node (ref "X1") (pin "4") (pinfunction "4_4") (pintype "passive"))
      (node (ref "X2") (pin "1") (pinfunction "1_1") (pintype "passive"))
    )
    (net (code "63") (name "RESET") (class "Default")
      (node (ref "C2") (pin "1") (pinfunction "1_1") (pintype "passive"))
      (node (ref "Q2") (pin "3") (pinfunction "C2_3") (pintype "passive"))
      (node (ref "R2") (pin "1") (pinfunction "1_1") (pintype "passive"))
      (node (ref "S4") (pin "1") (pinfunction "1_1") (pintype "passive"))
      (node (ref "U2") (pin "3") (pinfunction "EN_3") (pintype "passive"))
    )
    (net (code "64") (name "RTS") (class "Default")
      (node (ref "Q2") (pin "4") (pinfunction "E2_4") (pintype "passive"))
      (node (ref "R17") (pin "1") (pinfunction "1_1") (pintype "passive"))
      (node (ref "U7") (pin "19") (pinfunction "~{RTS}_19") (pintype "passive"))
    )
    (net (code "65") (name "RX") (class "Default")
      (node (ref "R11") (pin "2") (pinfunction "2_2") (pintype "passive"))
      (node (ref "U2") (pin "34") (pinfunction "RXD0_34") (pintype "passive"))
      (node (ref "U7") (pin "21") (pinfunction "TXD_21") (pintype "passive"))
    )
    (net (code "66") (name "SCL") (class "Default")
      (node (ref "I2C_IN") (pin "2") (pinfunction "2_2") (pintype "passive"))
      (node (ref "I2C_OUT") (pin "2") (pinfunction "2_2") (pintype "passive"))
      (node (ref "OLED") (pin "3") (pinfunction "SCL_3") (pintype "passive"))
      (node (ref "R4") (pin "2") (pinfunction "2_2") (pintype "passive"))
      (node (ref "U2") (pin "36") (pinfunction "IO22_36") (pintype "passive"))
      (node (ref "U4") (pin "7") (pinfunction "SCL_7") (pintype "passive"))
      (node (ref "U6") (pin "3") (pinfunction "SCL_3") (pintype "passive"))
    )
    (net (code "67") (name "SDA") (class "Default")
      (node (ref "I2C_IN") (pin "3") (pinfunction "3_3") (pintype "passive"))
      (node (ref "I2C_OUT") (pin "3") (pinfunction "3_3") (pintype "passive"))
      (node (ref "OLED") (pin "4") (pinfunction "SDA_4") (pintype "passive"))
      (node (ref "R5") (pin "2") (pinfunction "2_2") (pintype "passive"))
      (node (ref "U2") (pin "33") (pinfunction "IO21_33") (pintype "passive"))
      (node (ref "U4") (pin "8") (pinfunction "SDA_8") (pintype "passive"))
      (node (ref "U6") (pin "4") (pinfunction "SDA_4") (pintype "passive"))
    )
    (net (code "68") (name "T1") (class "Default")
      (node (ref "R29") (pin "1") (pinfunction "1_1") (pintype "passive"))
      (node (ref "RT1") (pin "2") (pinfunction "2_2") (pintype "passive"))
      (node (ref "U6") (pin "9") (pinfunction "A2_9") (pintype "passive"))
    )
    (net (code "69") (name "T2") (class "Default")
      (node (ref "R30") (pin "1") (pinfunction "1_1") (pintype "passive"))
      (node (ref "RT2") (pin "2") (pinfunction "2_2") (pintype "passive"))
      (node (ref "U6") (pin "10") (pinfunction "A3_10") (pintype "passive"))
    )
    (net (code "70") (name "TX") (class "Default")
      (node (ref "R12") (pin "2") (pinfunction "2_2") (pintype "passive"))
      (node (ref "U2") (pin "35") (pinfunction "TXD0_35") (pintype "passive"))
      (node (ref "U7") (pin "20") (pinfunction "RXD_20") (pintype "passive"))
    )
    (net (code "71") (name "VAUX") (class "Default")
      (node (ref "C18") (pin "1") (pinfunction "1_1") (pintype "passive"))
      (node (ref "J2") (pin "3") (pinfunction "3_3") (pintype "passive"))
      (node (ref "J3") (pin "3") (pinfunction "3_3") (pintype "passive"))
      (node (ref "TP1") (pin "1") (pinfunction "1_1") (pintype "passive"))
      (node (ref "U5") (pin "1") (pinfunction "VAUX_1") (pintype "passive"))
    )
    (net (code "72") (name "VIN") (class "Default")
      (node (ref "C7") (pin "1") (pinfunction "1_1") (pintype "passive"))
      (node (ref "D4") (pin "C") (pinfunction "C_C") (pintype "passive"))
      (node (ref "Q3") (pin "2") (pinfunction "S_2") (pintype "passive"))
      (node (ref "R8") (pin "1") (pinfunction "1_1") (pintype "passive"))
      (node (ref "U3") (pin "1") (pinfunction "VIN_1") (pintype "passive"))
    )
    (net (code "73") (name "VOUT") (class "Default")
      (node (ref "C22") (pin "1") (pinfunction "1_1") (pintype "passive"))
      (node (ref "C23") (pin "1") (pinfunction "1_1") (pintype "passive"))
      (node (ref "SW1") (pin "2") (pinfunction "2_2") (pintype "passive"))
      (node (ref "SW2") (pin "2") (pinfunction "2_2") (pintype "passive"))
      (node (ref "SW3") (pin "2") (pinfunction "2_2") (pintype "passive"))
      (node (ref "SW4") (pin "2") (pinfunction "2_2") (pintype "passive"))
      (node (ref "SW5") (pin "2") (pinfunction "2_2") (pintype "passive"))
      (node (ref "SW6") (pin "2") (pinfunction "2_2") (pintype "passive"))
      (node (ref "SW7") (pin "2") (pinfunction "2_2") (pintype "passive"))
      (node (ref "SW8") (pin "2") (pinfunction "2_2") (pintype "passive"))
      (node (ref "TP3") (pin "1") (pinfunction "1_1") (pintype "passive"))
      (node (ref "U5") (pin "3") (pinfunction "VOUT_3") (pintype "passive"))
      (node (ref "U6") (pin "8") (pinfunction "A1_8") (pintype "passive"))
    )
    (net (code "74") (name "VS1") (class "Default")
      (node (ref "J2") (pin "2") (pinfunction "2_2") (pintype "passive"))
      (node (ref "U5") (pin "8") (pinfunction "VS1_8") (pintype "passive"))
    )
    (net (code "75") (name "VS2") (class "Default")
      (node (ref "J3") (pin "2") (pinfunction "2_2") (pintype "passive"))
      (node (ref "U5") (pin "7") (pinfunction "VS2_7") (pintype "passive"))
    )
    (net (code "76") (name "V_BATT") (class "Default")
      (node (ref "C15") (pin "1") (pinfunction "1_1") (pintype "passive"))
      (node (ref "C6") (pin "1") (pinfunction "1_1") (pintype "passive"))
      (node (ref "PWR") (pin "1") (pinfunction "1_1") (pintype "passive"))
      (node (ref "Q3") (pin "3") (pinfunction "D_3") (pintype "passive"))
      (node (ref "U1") (pin "3") (pinfunction "VBAT_3") (pintype "passive"))
      (node (ref "U4") (pin "2") (pinfunction "CELL_2") (pintype "passive"))
      (node (ref "U4") (pin "3") (pinfunction "VDD_3") (pintype "passive"))
    )
    (net (code "77") (name "V_USB") (class "Default")
      (node (ref "C4") (pin "1") (pinfunction "1_1") (pintype "passive"))
      (node (ref "C8") (pin "1") (pinfunction "1_1") (pintype "passive"))
      (node (ref "D4") (pin "A") (pinfunction "A_A") (pintype "passive"))
      (node (ref "J1") (pin "A4") (pinfunction "VBUS_A4") (pintype "passive"))
      (node (ref "J1") (pin "A9") (pinfunction "VBUS_A9") (pintype "passive"))
      (node (ref "J1") (pin "B4") (pinfunction "VBUS_B4") (pintype "passive"))
      (node (ref "J1") (pin "B9") (pinfunction "VBUS_B9") (pintype "passive"))
      (node (ref "Q3") (pin "1") (pinfunction "G_1") (pintype "passive"))
      (node (ref "R3") (pin "1") (pinfunction "1_1") (pintype "passive"))
      (node (ref "R7") (pin "2") (pinfunction "2_2") (pintype "passive"))
      (node (ref "U1") (pin "4") (pinfunction "VDD_4") (pintype "passive"))
      (node (ref "U7") (pin "7") (pinfunction "REGIN_7") (pintype "passive"))
      (node (ref "U7") (pin "8") (pinfunction "VBUS_8") (pintype "passive"))
    )
    (net (code "78") (name "unconnected-(J1-SBUS1-PadA8)") (class "Default")
      (node (ref "J1") (pin "A8") (pinfunction "SBUS1_A8") (pintype "passive"))
    )
    (net (code "79") (name "unconnected-(J1-SBUS2-PadB8)") (class "Default")
      (node (ref "J1") (pin "B8") (pinfunction "SBUS2_B8") (pintype "passive"))
    )
    (net (code "80") (name "unconnected-(J6-DAT1-Pad8)") (class "Default")
      (node (ref "J6") (pin "8") (pinfunction "DAT1_8") (pintype "passive"))
    )
    (net (code "81") (name "unconnected-(J6-DAT2-Pad1)") (class "Default")
      (node (ref "J6") (pin "1") (pinfunction "DAT2_1") (pintype "passive"))
    )
    (net (code "82") (name "unconnected-(PWR-Pad3)") (class "Default")
      (node (ref "PWR") (pin "3") (pinfunction "3_3") (pintype "passive"))
    )
    (net (code "83") (name "unconnected-(U2-IO2-Pad24)") (class "Default")
      (node (ref "U2") (pin "24") (pinfunction "IO2_24") (pintype "passive"))
    )
    (net (code "84") (name "unconnected-(U2-IO4-Pad26)") (class "Default")
      (node (ref "U2") (pin "26") (pinfunction "IO4_26") (pintype "passive"))
    )
    (net (code "85") (name "unconnected-(U2-IO12-Pad14)") (class "Default")
      (node (ref "U2") (pin "14") (pinfunction "IO12_14") (pintype "passive"))
    )
    (net (code "86") (name "unconnected-(U2-IO13-Pad16)") (class "Default")
      (node (ref "U2") (pin "16") (pinfunction "IO13_16") (pintype "passive"))
    )
    (net (code "87") (name "unconnected-(U2-IO14-Pad13)") (class "Default")
      (node (ref "U2") (pin "13") (pinfunction "IO14_13") (pintype "passive"))
    )
    (net (code "88") (name "unconnected-(U2-IO15-Pad23)") (class "Default")
      (node (ref "U2") (pin "23") (pinfunction "IO15_23") (pintype "passive"))
    )
    (net (code "89") (name "unconnected-(U2-IO27-Pad12)") (class "Default")
      (node (ref "U2") (pin "12") (pinfunction "IO27_12") (pintype "passive"))
    )
    (net (code "90") (name "unconnected-(U2-IO32-Pad8)") (class "Default")
      (node (ref "U2") (pin "8") (pinfunction "IO32_8") (pintype "passive"))
    )
    (net (code "91") (name "unconnected-(U2-IO33-Pad9)") (class "Default")
      (node (ref "U2") (pin "9") (pinfunction "IO33_9") (pintype "passive"))
    )
    (net (code "92") (name "unconnected-(U2-IO34-Pad6)") (class "Default")
      (node (ref "U2") (pin "6") (pinfunction "IO34_6") (pintype "passive"))
    )
    (net (code "93") (name "unconnected-(U2-IO35-Pad7)") (class "Default")
      (node (ref "U2") (pin "7") (pinfunction "IO35_7") (pintype "passive"))
    )
    (net (code "94") (name "unconnected-(U2-NC-Pad17)") (class "Default")
      (node (ref "U2") (pin "17") (pinfunction "NC_17") (pintype "passive"))
    )
    (net (code "95") (name "unconnected-(U2-NC-Pad18)") (class "Default")
      (node (ref "U2") (pin "18") (pinfunction "NC_18") (pintype "passive"))
    )
    (net (code "96") (name "unconnected-(U2-NC-Pad19)") (class "Default")
      (node (ref "U2") (pin "19") (pinfunction "NC_19") (pintype "passive"))
    )
    (net (code "97") (name "unconnected-(U2-NC-Pad20)") (class "Default")
      (node (ref "U2") (pin "20") (pinfunction "NC_20") (pintype "passive"))
    )
    (net (code "98") (name "unconnected-(U2-NC-Pad21)") (class "Default")
      (node (ref "U2") (pin "21") (pinfunction "NC_21") (pintype "passive"))
    )
    (net (code "99") (name "unconnected-(U2-NC-Pad22)") (class "Default")
      (node (ref "U2") (pin "22") (pinfunction "NC_22") (pintype "passive"))
    )
    (net (code "100") (name "unconnected-(U2-NC1-Pad32)") (class "Default")
      (node (ref "U2") (pin "32") (pinfunction "NC1_32") (pintype "passive"))
    )
    (net (code "101") (name "unconnected-(U4-~{ALERT}-Pad5)") (class "Default")
      (node (ref "U4") (pin "5") (pinfunction "~{ALERT}_5") (pintype "passive"))
    )
    (net (code "102") (name "unconnected-(U5-VOUT2-Pad4)") (class "Default")
      (node (ref "U5") (pin "4") (pinfunction "VOUT2_4") (pintype "passive"))
    )
    (net (code "103") (name "unconnected-(U5-VOUT2_EN-Pad9)") (class "Default")
      (node (ref "U5") (pin "9") (pinfunction "VOUT2_EN_9") (pintype "passive"))
    )
    (net (code "104") (name "unconnected-(U6-ADDR-Pad5)") (class "Default")
      (node (ref "U6") (pin "5") (pinfunction "ADDR_5") (pintype "passive"))
    )
    (net (code "105") (name "unconnected-(U6-ALRT-Pad6)") (class "Default")
      (node (ref "U6") (pin "6") (pinfunction "ALRT_6") (pintype "passive"))
    )
    (net (code "106") (name "unconnected-(U7-GPIO.0-Pad14)") (class "Default")
      (node (ref "U7") (pin "14") (pinfunction "GPIO.0_14") (pintype "passive"))
    )
    (net (code "107") (name "unconnected-(U7-GPIO.1-Pad13)") (class "Default")
      (node (ref "U7") (pin "13") (pinfunction "GPIO.1_13") (pintype "passive"))
    )
    (net (code "108") (name "unconnected-(U7-GPIO.2-Pad12)") (class "Default")
      (node (ref "U7") (pin "12") (pinfunction "GPIO.2_12") (pintype "passive"))
    )
    (net (code "109") (name "unconnected-(U7-GPIO.3-Pad11)") (class "Default")
      (node (ref "U7") (pin "11") (pinfunction "GPIO.3_11") (pintype "passive"))
    )
    (net (code "110") (name "unconnected-(U7-SUSPEND-Pad17)") (class "Default")
      (node (ref "U7") (pin "17") (pinfunction "SUSPEND_17") (pintype "passive"))
    )
    (net (code "111") (name "unconnected-(U7-VPP-Pad16)") (class "Default")
      (node (ref "U7") (pin "16") (pinfunction "VPP_16") (pintype "passive"))
    )
    (net (code "112") (name "unconnected-(U7-~{CTS}-Pad18)") (class "Default")
      (node (ref "U7") (pin "18") (pinfunction "~{CTS}_18") (pintype "passive"))
    )
    (net (code "113") (name "unconnected-(U7-~{DCD}-Pad24)") (class "Default")
      (node (ref "U7") (pin "24") (pinfunction "~{DCD}_24") (pintype "passive"))
    )
    (net (code "114") (name "unconnected-(U7-~{DSR}-Pad22)") (class "Default")
      (node (ref "U7") (pin "22") (pinfunction "~{DSR}_22") (pintype "passive"))
    )
    (net (code "115") (name "unconnected-(U7-~{RI}-Pad1)") (class "Default")
      (node (ref "U7") (pin "1") (pinfunction "~{RI}_1") (pintype "passive"))
    )
    (net (code "116") (name "unconnected-(U7-~{SUSPEND!}-Pad15)") (class "Default")
      (node (ref "U7") (pin "15") (pinfunction "~{SUSPEND!}_15") (pintype "passive"))
    )
  )
)
